# LCD_Display.net
KiCad netlist of a schematic drawn in Altium Designer
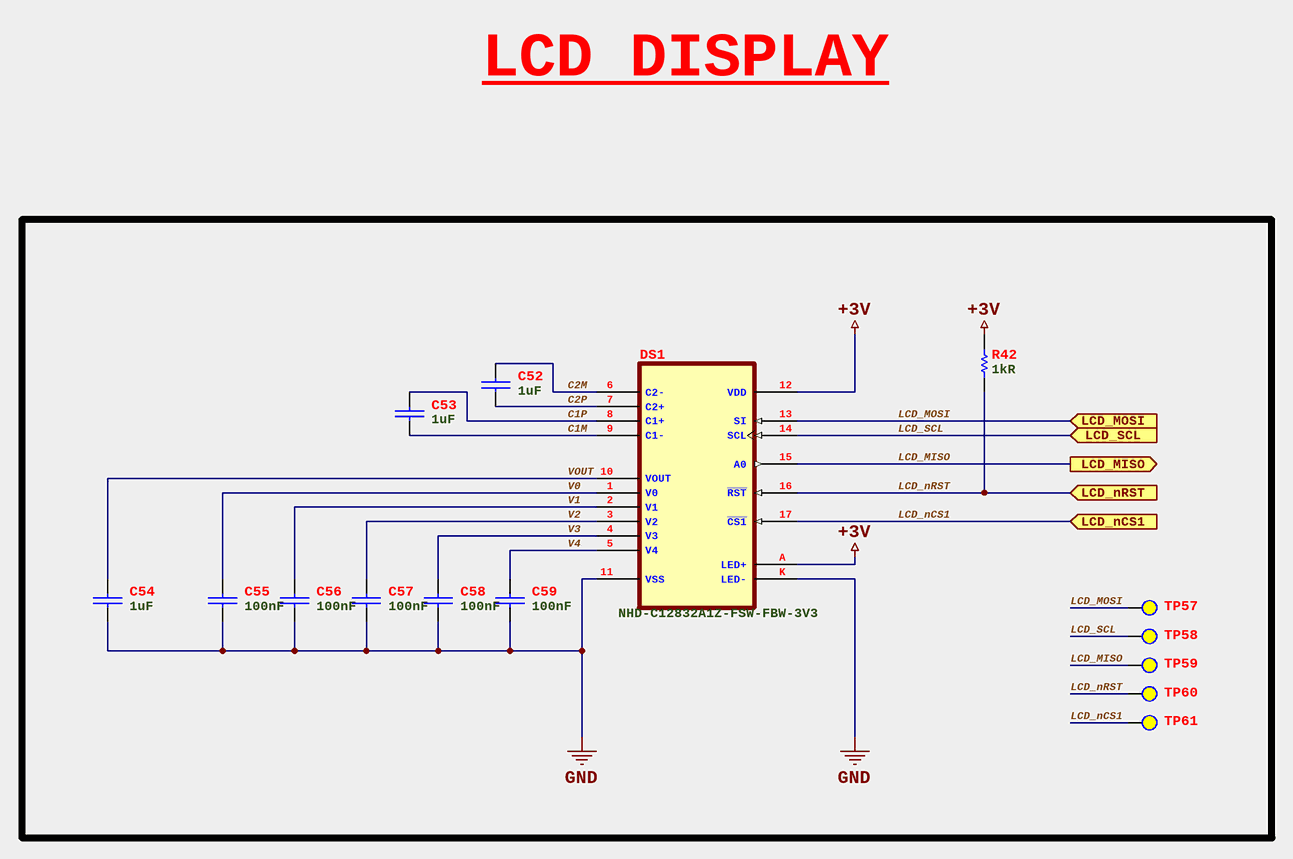
[diagram p0: LCD Display.SchDoc]

(export (version "E")
  (design (tool "Eeschema 10.0.6"))
  (components
    (comp (ref "C52")
      (value "1uF")
      (footprint "CAP_0805")
      (description "1 µF ±10% 16V Ceramic Capacitor X7R 0603 (1608 Metric)")
      (fields
        (field (name "MANUFACTURER") "Yageo")
        (field (name "MANUFACTURER PART NUMBER") "CC0603KRX7R7BB105")
      )
      (libsource (lib "Cellar Watchdog") (part "CAP_1uF-16V-10%_0603"))
    )
    (comp (ref "C53")
      (value "1uF")
      (footprint "CAP_0805")
      (description "1 µF ±10% 16V Ceramic Capacitor X7R 0603 (1608 Metric)")
      (fields
        (field (name "MANUFACTURER") "Yageo")
        (field (name "MANUFACTURER PART NUMBER") "CC0603KRX7R7BB105")
      )
      (libsource (lib "Cellar Watchdog") (part "CAP_1uF-16V-10%_0603"))
    )
    (comp (ref "C54")
      (value "1uF")
      (footprint "CAP_0805")
      (description "1 µF ±10% 16V Ceramic Capacitor X7R 0603 (1608 Metric)")
      (fields
        (field (name "MANUFACTURER") "Yageo")
        (field (name "MANUFACTURER PART NUMBER") "CC0603KRX7R7BB105")
      )
      (libsource (lib "Cellar Watchdog") (part "CAP_1uF-16V-10%_0603"))
    )
    (comp (ref "C55")
      (value "100nF")
      (footprint "CAP_0603")
      (description "0.1 µF ±10% 50V Ceramic Capacitor X7R 0603 (1608 Metric)")
      (fields
        (field (name "MANUFACTURER") "Yageo")
        (field (name "MANUFACTURER PART NUMBER") "CC0603KRX7R9BB104")
      )
      (libsource (lib "Cellar Watchdog") (part "CAP_0.1uF-50V-10%_0603"))
    )
    (comp (ref "C56")
      (value "100nF")
      (footprint "CAP_0603")
      (description "0.1 µF ±10% 50V Ceramic Capacitor X7R 0603 (1608 Metric)")
      (fields
        (field (name "MANUFACTURER") "Yageo")
        (field (name "MANUFACTURER PART NUMBER") "CC0603KRX7R9BB104")
      )
      (libsource (lib "Cellar Watchdog") (part "CAP_0.1uF-50V-10%_0603"))
    )
    (comp (ref "C57")
      (value "100nF")
      (footprint "CAP_0603")
      (description "0.1 µF ±10% 50V Ceramic Capacitor X7R 0603 (1608 Metric)")
      (fields
        (field (name "MANUFACTURER") "Yageo")
        (field (name "MANUFACTURER PART NUMBER") "CC0603KRX7R9BB104")
      )
      (libsource (lib "Cellar Watchdog") (part "CAP_0.1uF-50V-10%_0603"))
    )
    (comp (ref "C58")
      (value "100nF")
      (footprint "CAP_0603")
      (description "0.1 µF ±10% 50V Ceramic Capacitor X7R 0603 (1608 Metric)")
      (fields
        (field (name "MANUFACTURER") "Yageo")
        (field (name "MANUFACTURER PART NUMBER") "CC0603KRX7R9BB104")
      )
      (libsource (lib "Cellar Watchdog") (part "CAP_0.1uF-50V-10%_0603"))
    )
    (comp (ref "C59")
      (value "100nF")
      (footprint "CAP_0603")
      (description "0.1 µF ±10% 50V Ceramic Capacitor X7R 0603 (1608 Metric)")
      (fields
        (field (name "MANUFACTURER") "Yageo")
        (field (name "MANUFACTURER PART NUMBER") "CC0603KRX7R9BB104")
      )
      (libsource (lib "Cellar Watchdog") (part "CAP_0.1uF-50V-10%_0603"))
    )
    (comp (ref "DS1")
      (value "NHD-C12832A1Z-FSW-FBW-3V3")
      (footprint "LCD_NHD-C12832A1Z-FSW-FBW-3V3")
      (fields (field (name "MANUFACTURER") "Newhaven Display"))
      (libsource (lib "Cellar Watchdog") (part "LCD_NHD-C12832A1Z-FSW-FBW-3V3"))
    )
    (comp (ref "R42")
      (value "1kR")
      (footprint "RES_0603")
      (description "1 kOhms ±1% 0.1W, 1/10W Chip Resistor 0603 (1608 Metric) Moisture Resistant Thick Film")
      (fields
        (field (name "MANUFACTURER") "Yageo")
        (field (name "MANUFACTURER PART NUMBER") "RC0603FR-071KL")
      )
      (libsource (lib "Cellar Watchdog") (part "RES_1kR-100mW-1%_0603"))
    )
    (comp (ref "TP57")
      (value "LCD_MOSI")
      (footprint "TEST POINT PAD")
      (description "PCB Test Point")
      (libsource (lib "Cellar Watchdog") (part "Test Point"))
    )
    (comp (ref "TP58")
      (value "LCD_SCL")
      (footprint "TEST POINT PAD")
      (description "PCB Test Point")
      (libsource (lib "Cellar Watchdog") (part "Test Point"))
    )
    (comp (ref "TP59")
      (value "LCD_MISO")
      (footprint "TEST POINT PAD")
      (description "PCB Test Point")
      (libsource (lib "Cellar Watchdog") (part "Test Point"))
    )
    (comp (ref "TP60")
      (value "LCD_nRST")
      (footprint "TEST POINT PAD")
      (description "PCB Test Point")
      (libsource (lib "Cellar Watchdog") (part "Test Point"))
    )
    (comp (ref "TP61")
      (value "LCD_nCS1")
      (footprint "TEST POINT PAD")
      (description "PCB Test Point")
      (libsource (lib "Cellar Watchdog") (part "Test Point"))
    )
  )
  (nets
    (net (code "1") (name "+3V") (class "Default")
      (node (ref "DS1") (pin "12") (pinfunction "VDD_12") (pintype "power_in"))
      (node (ref "DS1") (pin "A") (pinfunction "LED+_A") (pintype "power_in"))
      (node (ref "R42") (pin "2") (pinfunction "2_2") (pintype "passive"))
    )
    (net (code "2") (name "/C1M") (class "Default")
      (node (ref "C53") (pin "2") (pinfunction "2_2") (pintype "passive"))
      (node (ref "DS1") (pin "9") (pinfunction "C1-_9") (pintype "power_in"))
    )
    (net (code "3") (name "/C1P") (class "Default")
      (node (ref "C53") (pin "1") (pinfunction "1_1") (pintype "passive"))
      (node (ref "DS1") (pin "8") (pinfunction "C1+_8") (pintype "power_in"))
    )
    (net (code "4") (name "/C2M") (class "Default")
      (node (ref "C52") (pin "1") (pinfunction "1_1") (pintype "passive"))
      (node (ref "DS1") (pin "6") (pinfunction "C2-_6") (pintype "power_in"))
    )
    (net (code "5") (name "/C2P") (class "Default")
      (node (ref "C52") (pin "2") (pinfunction "2_2") (pintype "passive"))
      (node (ref "DS1") (pin "7") (pinfunction "C2+_7") (pintype "power_in"))
    )
    (net (code "6") (name "/LCD_MISO") (class "Default")
      (node (ref "DS1") (pin "15") (pinfunction "A0_15") (pintype "output"))
      (node (ref "TP59") (pin "TP") (pinfunction "TP_TP") (pintype "passive"))
    )
    (net (code "7") (name "/LCD_MOSI") (class "Default")
      (node (ref "DS1") (pin "13") (pinfunction "SI_13") (pintype "input"))
      (node (ref "TP57") (pin "TP") (pinfunction "TP_TP") (pintype "passive"))
    )
    (net (code "8") (name "/LCD_SCL") (class "Default")
      (node (ref "DS1") (pin "14") (pinfunction "SCL_14") (pintype "input"))
      (node (ref "TP58") (pin "TP") (pinfunction "TP_TP") (pintype "passive"))
    )
    (net (code "9") (name "/LCD_nCS1") (class "Default")
      (node (ref "DS1") (pin "17") (pinfunction "CS1_17") (pintype "input"))
      (node (ref "TP61") (pin "TP") (pinfunction "TP_TP") (pintype "passive"))
    )
    (net (code "10") (name "/LCD_nRST") (class "Default")
      (node (ref "DS1") (pin "16") (pinfunction "RST_16") (pintype "input"))
      (node (ref "R42") (pin "1") (pinfunction "1_1") (pintype "passive"))
      (node (ref "TP60") (pin "TP") (pinfunction "TP_TP") (pintype "passive"))
    )
    (net (code "11") (name "/V0") (class "Default")
      (node (ref "C55") (pin "1") (pinfunction "1_1") (pintype "passive"))
      (node (ref "DS1") (pin "1") (pinfunction "V0_1") (pintype "power_in"))
    )
    (net (code "12") (name "/V1") (class "Default")
      (node (ref "C56") (pin "1") (pinfunction "1_1") (pintype "passive"))
      (node (ref "DS1") (pin "2") (pinfunction "V1_2") (pintype "power_in"))
    )
    (net (code "13") (name "/V2") (class "Default")
      (node (ref "C57") (pin "1") (pinfunction "1_1") (pintype "passive"))
      (node (ref "DS1") (pin "3") (pinfunction "V2_3") (pintype "power_in"))
    )
    (net (code "14") (name "/V3") (class "Default")
      (node (ref "C58") (pin "1") (pinfunction "1_1") (pintype "passive"))
      (node (ref "DS1") (pin "4") (pinfunction "V3_4") (pintype "power_in"))
    )
    (net (code "15") (name "/V4") (class "Default")
      (node (ref "C59") (pin "1") (pinfunction "1_1") (pintype "passive"))
      (node (ref "DS1") (pin "5") (pinfunction "V4_5") (pintype "power_in"))
    )
    (net (code "16") (name "/VOUT") (class "Default")
      (node (ref "C54") (pin "1") (pinfunction "1_1") (pintype "passive"))
      (node (ref "DS1") (pin "10") (pinfunction "VOUT_10") (pintype "power_in"))
    )
    (net (code "17") (name "GND") (class "Default")
      (node (ref "C54") (pin "2") (pinfunction "2_2") (pintype "passive"))
      (node (ref "C55") (pin "2") (pinfunction "2_2") (pintype "passive"))
      (node (ref "C56") (pin "2") (pinfunction "2_2") (pintype "passive"))
      (node (ref "C57") (pin "2") (pinfunction "2_2") (pintype "passive"))
      (node (ref "C58") (pin "2") (pinfunction "2_2") (pintype "passive"))
      (node (ref "C59") (pin "2") (pinfunction "2_2") (pintype "passive"))
      (node (ref "DS1") (pin "11") (pinfunction "VSS_11") (pintype "power_in"))
      (node (ref "DS1") (pin "K") (pinfunction "LED-_K") (pintype "power_in"))
    )
  )
)
